# APD_flex_R02.net
KiCad netlist of a schematic drawn in Altium Designer
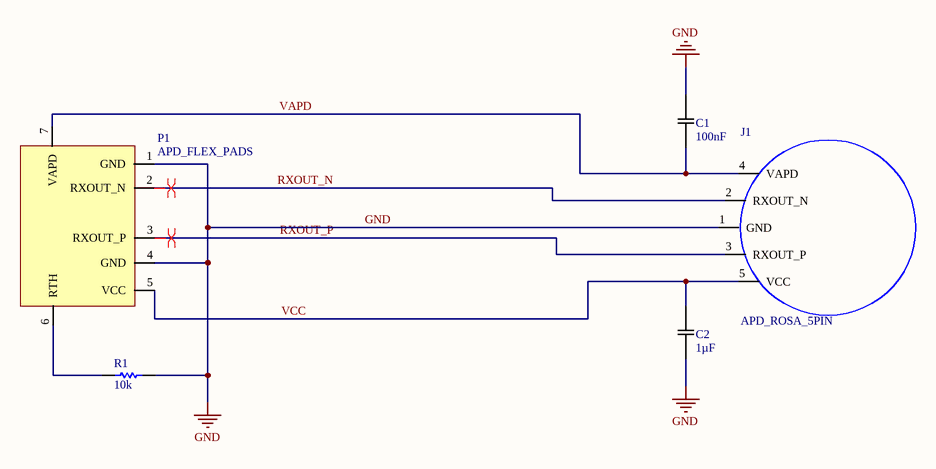
[diagram p0: APD_flex_R02.SchDoc]

(export (version "E")
  (design (tool "Eeschema 10.0.6"))
  (components
    (comp (ref "C1")
      (value "100nF")
      (footprint "0603")
      (description "100nF_0603")
      (fields
        (field (name "MANUFACTURER") "Murata Electronics North America")
        (field (name "MANUFACTURER PART NUMBER") "GRM188R72A104KA35D")
      )
      (libsource (lib "APD_Alpha2_R02") (part "CAP_100nF_0603"))
    )
    (comp (ref "C2")
      (value "1µF")
      (footprint "0402")
      (description "1µF_0402")
      (fields
        (field (name "MANUFACTURER") "Samsung Electro-Mechanics")
        (field (name "MANUFACTURER PART NUMBER") "CL05A105KP5NNNC")
      )
      (libsource (lib "APD_Alpha2_R02") (part "CAP_1µF_0402"))
    )
    (comp (ref "J1")
      (value "APD_ROSA_5PIN")
      (footprint "APD_5PINS - Pin F")
      (libsource (lib "APD_Alpha2_R01") (part "APD_ROSA_5PIN"))
    )
    (comp (ref "P1")
      (value "APD_FLEX_PADS")
      (footprint "FLEX_7PADS - new_design")
      (libsource (lib "APD_Alpha2_R01") (part "APD_FLEX_PADS"))
    )
    (comp (ref "R1")
      (value "10k")
      (footprint "0402")
      (description "10K_0402_Termistor")
      (fields
        (field (name "MANUFACTURER") "Vishay BC Components")
        (field (name "MANUFACTURER PART NUMBER") "NTCS0402E3103FLT")
      )
      (libsource (lib "APD_Alpha2_R02") (part "RES_10k_0402"))
    )
  )
  (nets
    (net (code "1") (name "/RXOUT_N") (class "Default")
      (node (ref "J1") (pin "2") (pinfunction "RXOUT_N_2") (pintype "passive"))
      (node (ref "P1") (pin "2") (pinfunction "RXOUT_N_2") (pintype "passive"))
    )
    (net (code "2") (name "/RXOUT_P") (class "Default")
      (node (ref "J1") (pin "3") (pinfunction "RXOUT_P_3") (pintype "passive"))
      (node (ref "P1") (pin "3") (pinfunction "RXOUT_P_3") (pintype "passive"))
    )
    (net (code "3") (name "/VAPD") (class "Default")
      (node (ref "C1") (pin "1") (pinfunction "1_1") (pintype "passive"))
      (node (ref "J1") (pin "4") (pinfunction "VAPD_4") (pintype "passive"))
      (node (ref "P1") (pin "7") (pinfunction "VAPD_7") (pintype "passive"))
    )
    (net (code "4") (name "/VCC") (class "Default")
      (node (ref "C2") (pin "1") (pinfunction "1_1") (pintype "passive"))
      (node (ref "J1") (pin "5") (pinfunction "VCC_5") (pintype "passive"))
      (node (ref "P1") (pin "5") (pinfunction "VCC_5") (pintype "passive"))
    )
    (net (code "5") (name "GND") (class "Default")
      (node (ref "C1") (pin "2") (pinfunction "2_2") (pintype "passive"))
      (node (ref "C2") (pin "2") (pinfunction "2_2") (pintype "passive"))
      (node (ref "J1") (pin "1") (pinfunction "GND_1") (pintype "passive"))
      (node (ref "P1") (pin "1") (pinfunction "GND_1") (pintype "passive"))
      (node (ref "P1") (pin "4") (pinfunction "GND_4") (pintype "passive"))
      (node (ref "R1") (pin "2") (pinfunction "2_2") (pintype "passive"))
    )
    (net (code "6") (name "Net-(P1-RTH)") (class "Default")
      (node (ref "P1") (pin "6") (pinfunction "RTH_6") (pintype "passive"))
      (node (ref "R1") (pin "1") (pinfunction "1_1") (pintype "passive"))
    )
  )
)
